# config-bank3.net
KiCad netlist of a schematic drawn in Altium Designer
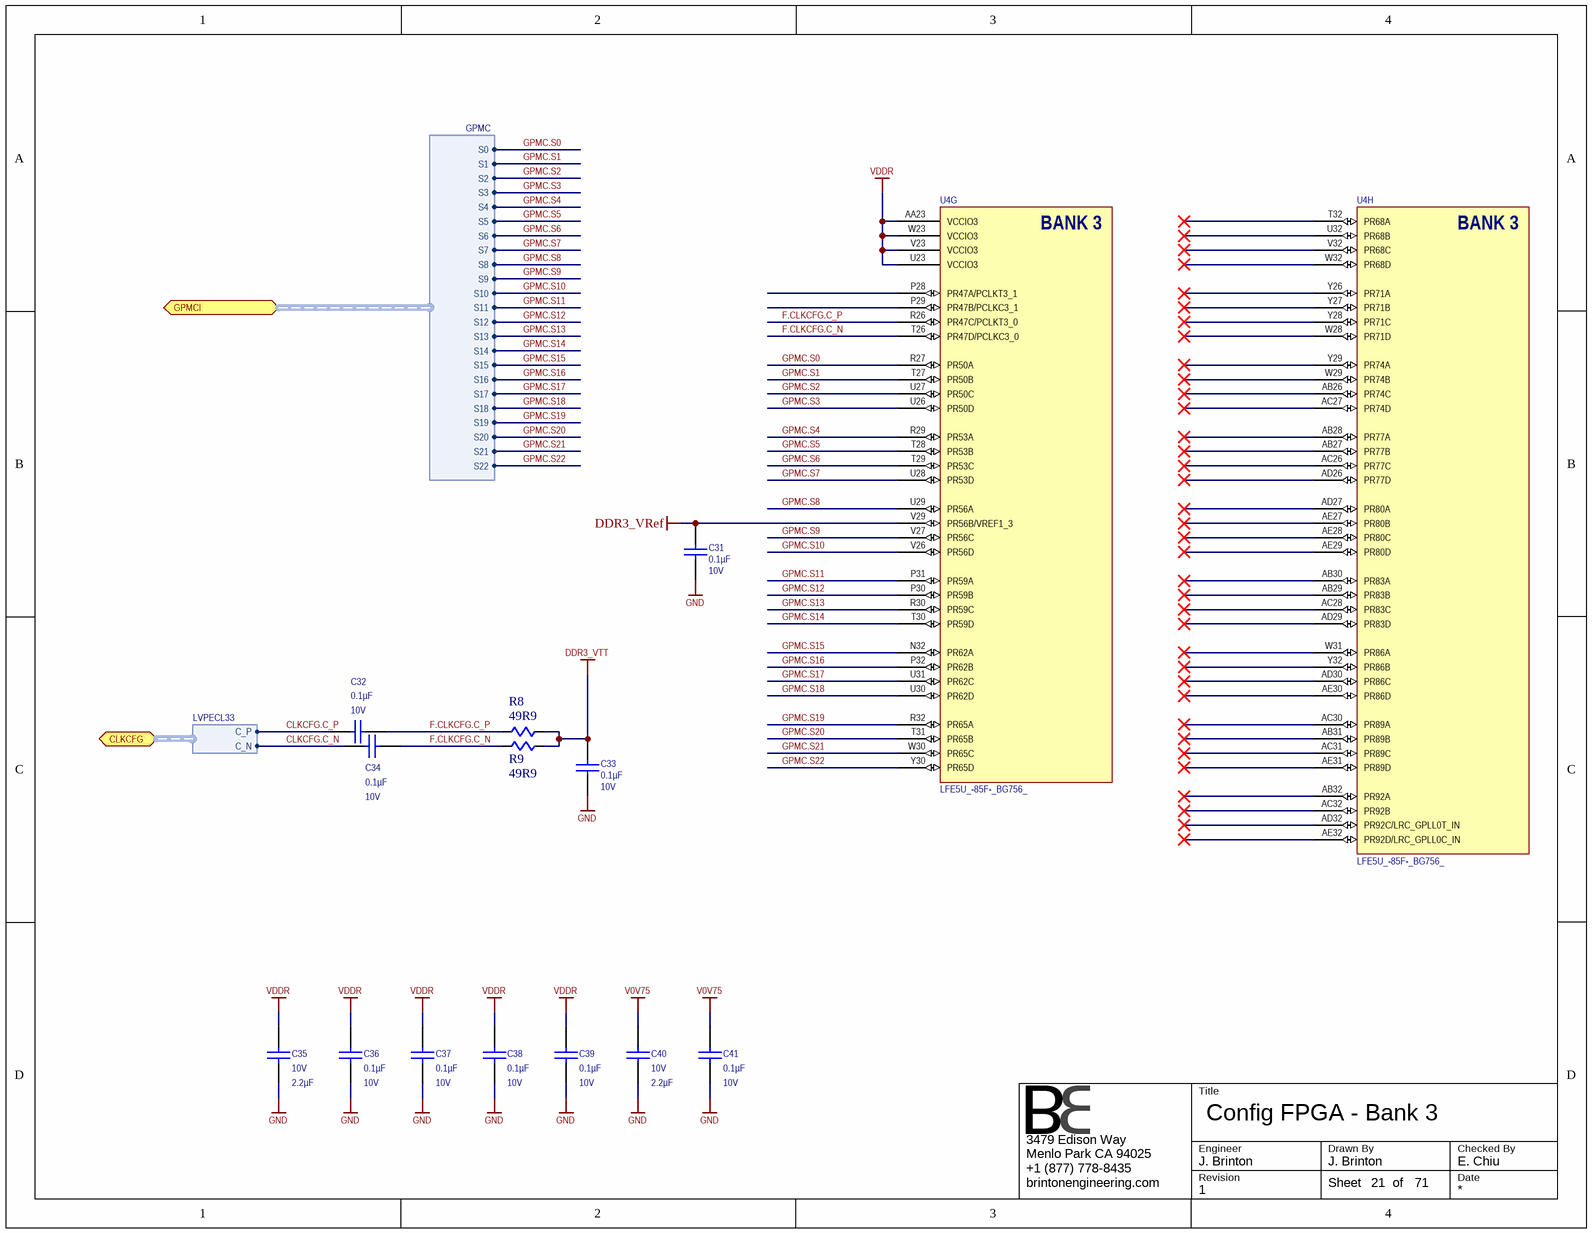
[diagram p0: config-bank3.SchDoc]

(export (version "E")
  (design (tool "Eeschema 10.0.6"))
  (components
    (comp (ref "C31")
      (value "GRM155R71A104KA01J")
      (footprint "CAPC1005X56N")
      (description "CAP CER 0.1UF 10V 10% X7R 0402")
      (fields
        (field (name "MANUFACTURER") "Murata Electronics North America")
        (field (name "TOLERANCE") "±10%")
        (field (name "CAPACITANCE") "0.1µF")
        (field (name "VOLTAGE - RATED") "10V")
      )
      (libsource (lib "murata") (part "GRM155R71A104KA01J"))
    )
    (comp (ref "C32")
      (value "GRM155R71A104KA01J")
      (footprint "CAPC1005X56N")
      (description "CAP CER 0.1UF 10V 10% X7R 0402")
      (fields
        (field (name "MANUFACTURER") "Murata Electronics North America")
        (field (name "TOLERANCE") "±10%")
        (field (name "CAPACITANCE") "0.1µF")
        (field (name "VOLTAGE - RATED") "10V")
      )
      (libsource (lib "murata") (part "GRM155R71A104KA01J"))
    )
    (comp (ref "C33")
      (value "GRM155R71A104KA01J")
      (footprint "CAPC1005X56N")
      (description "CAP CER 0.1UF 10V 10% X7R 0402")
      (fields
        (field (name "MANUFACTURER") "Murata Electronics North America")
        (field (name "TOLERANCE") "±10%")
        (field (name "CAPACITANCE") "0.1µF")
        (field (name "VOLTAGE - RATED") "10V")
      )
      (libsource (lib "murata") (part "GRM155R71A104KA01J"))
    )
    (comp (ref "C34")
      (value "GRM155R71A104KA01J")
      (footprint "CAPC1005X56N")
      (description "CAP CER 0.1UF 10V 10% X7R 0402")
      (fields
        (field (name "MANUFACTURER") "Murata Electronics North America")
        (field (name "TOLERANCE") "±10%")
        (field (name "CAPACITANCE") "0.1µF")
        (field (name "VOLTAGE - RATED") "10V")
      )
      (libsource (lib "murata") (part "GRM155R71A104KA01J"))
    )
    (comp (ref "C35")
      (value "GRM188R71A225KE15D")
      (footprint "CAPC1608X90N")
      (description "CAP CER 2.2UF 10V 10% X7R 0603")
      (fields
        (field (name "MANUFACTURER") "Murata Electronics North America")
        (field (name "TOLERANCE") "±10%")
        (field (name "VOLTAGE - RATED") "10V")
        (field (name "CAPACITANCE") "2.2µF")
      )
      (libsource (lib "murata") (part "GRM188R71A225KE15D"))
    )
    (comp (ref "C36")
      (value "GRM155R71A104KA01J")
      (footprint "CAPC1005X56N")
      (description "CAP CER 0.1UF 10V 10% X7R 0402")
      (fields
        (field (name "MANUFACTURER") "Murata Electronics North America")
        (field (name "TOLERANCE") "±10%")
        (field (name "CAPACITANCE") "0.1µF")
        (field (name "VOLTAGE - RATED") "10V")
      )
      (libsource (lib "murata") (part "GRM155R71A104KA01J"))
    )
    (comp (ref "C37")
      (value "GRM155R71A104KA01J")
      (footprint "CAPC1005X56N")
      (description "CAP CER 0.1UF 10V 10% X7R 0402")
      (fields
        (field (name "MANUFACTURER") "Murata Electronics North America")
        (field (name "TOLERANCE") "±10%")
        (field (name "CAPACITANCE") "0.1µF")
        (field (name "VOLTAGE - RATED") "10V")
      )
      (libsource (lib "murata") (part "GRM155R71A104KA01J"))
    )
    (comp (ref "C38")
      (value "GRM155R71A104KA01J")
      (footprint "CAPC1005X56N")
      (description "CAP CER 0.1UF 10V 10% X7R 0402")
      (fields
        (field (name "MANUFACTURER") "Murata Electronics North America")
        (field (name "TOLERANCE") "±10%")
        (field (name "CAPACITANCE") "0.1µF")
        (field (name "VOLTAGE - RATED") "10V")
      )
      (libsource (lib "murata") (part "GRM155R71A104KA01J"))
    )
    (comp (ref "C39")
      (value "GRM155R71A104KA01J")
      (footprint "CAPC1005X56N")
      (description "CAP CER 0.1UF 10V 10% X7R 0402")
      (fields
        (field (name "MANUFACTURER") "Murata Electronics North America")
        (field (name "TOLERANCE") "±10%")
        (field (name "CAPACITANCE") "0.1µF")
        (field (name "VOLTAGE - RATED") "10V")
      )
      (libsource (lib "murata") (part "GRM155R71A104KA01J"))
    )
    (comp (ref "C40")
      (value "GRM188R71A225KE15D")
      (footprint "CAPC1608X90N")
      (description "CAP CER 2.2UF 10V 10% X7R 0603")
      (fields
        (field (name "MANUFACTURER") "Murata Electronics North America")
        (field (name "TOLERANCE") "±10%")
        (field (name "VOLTAGE - RATED") "10V")
        (field (name "CAPACITANCE") "2.2µF")
      )
      (libsource (lib "murata") (part "GRM188R71A225KE15D"))
    )
    (comp (ref "C41")
      (value "GRM155R71A104KA01J")
      (footprint "CAPC1005X56N")
      (description "CAP CER 0.1UF 10V 10% X7R 0402")
      (fields
        (field (name "MANUFACTURER") "Murata Electronics North America")
        (field (name "TOLERANCE") "±10%")
        (field (name "CAPACITANCE") "0.1µF")
        (field (name "VOLTAGE - RATED") "10V")
      )
      (libsource (lib "murata") (part "GRM155R71A104KA01J"))
    )
    (comp (ref "R8")
      (value "49R9")
      (footprint "RESC1005N-0402")
      (description "Res 49.9R 1/10W 1% 0402")
      (fields (field (name "MFG") "Panasonic"))
      (libsource (lib "Kron Library Rev 3") (part "ERJ-2RKF49R9X"))
    )
    (comp (ref "R9")
      (value "49R9")
      (footprint "RESC1005N-0402")
      (description "Res 49.9R 1/10W 1% 0402")
      (fields (field (name "MFG") "Panasonic"))
      (libsource (lib "Kron Library Rev 3") (part "ERJ-2RKF49R9X"))
    )
    (comp (ref "U4")
      (value "LFE5U_-85F-_BG756_")
      (footprint "lattice:caBGA756")
      (description "ECP5 FPGA, 85k LUT, 756-caBGA")
      (fields (field (name "MANUFACTURER") "Lattice Semiconductor"))
      (libsource (lib "lattice") (part "LFE5U_-85F-_BG756_"))
    )
  )
  (nets
    (net (code "3") (name "/CLKCFG.C_N") (class "Default")
      (node (ref "C34") (pin "2") (pinfunction "2_2") (pintype "passive"))
    )
    (net (code "4") (name "/CLKCFG.C_P") (class "Default")
      (node (ref "C32") (pin "2") (pinfunction "2_2") (pintype "passive"))
    )
    (net (code "5") (name "/F.CLKCFG.C_N") (class "Default")
      (node (ref "C34") (pin "1") (pinfunction "1_1") (pintype "passive"))
      (node (ref "R9") (pin "1") (pintype "passive"))
      (node (ref "U4") (pin "T26") (pinfunction "PR47D/PCLKC3_0_T26") (pintype "bidirectional"))
    )
    (net (code "6") (name "/F.CLKCFG.C_P") (class "Default")
      (node (ref "C32") (pin "1") (pinfunction "1_1") (pintype "passive"))
      (node (ref "R8") (pin "1") (pintype "passive"))
      (node (ref "U4") (pin "R26") (pinfunction "PR47C/PCLKT3_0_R26") (pintype "bidirectional"))
    )
    (net (code "7") (name "/GPMC.S0") (class "Default")
      (node (ref "U4") (pin "R27") (pinfunction "PR50A_R27") (pintype "bidirectional"))
    )
    (net (code "8") (name "/GPMC.S1") (class "Default")
      (node (ref "U4") (pin "T27") (pinfunction "PR50B_T27") (pintype "bidirectional"))
    )
    (net (code "9") (name "/GPMC.S2") (class "Default")
      (node (ref "U4") (pin "U27") (pinfunction "PR50C_U27") (pintype "bidirectional"))
    )
    (net (code "10") (name "/GPMC.S3") (class "Default")
      (node (ref "U4") (pin "U26") (pinfunction "PR50D_U26") (pintype "bidirectional"))
    )
    (net (code "11") (name "/GPMC.S4") (class "Default")
      (node (ref "U4") (pin "R29") (pinfunction "PR53A_R29") (pintype "bidirectional"))
    )
    (net (code "12") (name "/GPMC.S5") (class "Default")
      (node (ref "U4") (pin "T28") (pinfunction "PR53B_T28") (pintype "bidirectional"))
    )
    (net (code "13") (name "/GPMC.S6") (class "Default")
      (node (ref "U4") (pin "T29") (pinfunction "PR53C_T29") (pintype "bidirectional"))
    )
    (net (code "14") (name "/GPMC.S7") (class "Default")
      (node (ref "U4") (pin "U28") (pinfunction "PR53D_U28") (pintype "bidirectional"))
    )
    (net (code "15") (name "/GPMC.S8") (class "Default")
      (node (ref "U4") (pin "U29") (pinfunction "PR56A_U29") (pintype "bidirectional"))
    )
    (net (code "16") (name "/GPMC.S9") (class "Default")
      (node (ref "U4") (pin "V27") (pinfunction "PR56C_V27") (pintype "bidirectional"))
    )
    (net (code "17") (name "/GPMC.S10") (class "Default")
      (node (ref "U4") (pin "V26") (pinfunction "PR56D_V26") (pintype "bidirectional"))
    )
    (net (code "18") (name "/GPMC.S11") (class "Default")
      (node (ref "U4") (pin "P31") (pinfunction "PR59A_P31") (pintype "bidirectional"))
    )
    (net (code "19") (name "/GPMC.S12") (class "Default")
      (node (ref "U4") (pin "P30") (pinfunction "PR59B_P30") (pintype "bidirectional"))
    )
    (net (code "20") (name "/GPMC.S13") (class "Default")
      (node (ref "U4") (pin "R30") (pinfunction "PR59C_R30") (pintype "bidirectional"))
    )
    (net (code "21") (name "/GPMC.S14") (class "Default")
      (node (ref "U4") (pin "T30") (pinfunction "PR59D_T30") (pintype "bidirectional"))
    )
    (net (code "22") (name "/GPMC.S15") (class "Default")
      (node (ref "U4") (pin "N32") (pinfunction "PR62A_N32") (pintype "bidirectional"))
    )
    (net (code "23") (name "/GPMC.S16") (class "Default")
      (node (ref "U4") (pin "P32") (pinfunction "PR62B_P32") (pintype "bidirectional"))
    )
    (net (code "24") (name "/GPMC.S17") (class "Default")
      (node (ref "U4") (pin "U31") (pinfunction "PR62C_U31") (pintype "bidirectional"))
    )
    (net (code "25") (name "/GPMC.S18") (class "Default")
      (node (ref "U4") (pin "U30") (pinfunction "PR62D_U30") (pintype "bidirectional"))
    )
    (net (code "26") (name "/GPMC.S19") (class "Default")
      (node (ref "U4") (pin "R32") (pinfunction "PR65A_R32") (pintype "bidirectional"))
    )
    (net (code "27") (name "/GPMC.S20") (class "Default")
      (node (ref "U4") (pin "T31") (pinfunction "PR65B_T31") (pintype "bidirectional"))
    )
    (net (code "28") (name "/GPMC.S21") (class "Default")
      (node (ref "U4") (pin "W30") (pinfunction "PR65C_W30") (pintype "bidirectional"))
    )
    (net (code "29") (name "/GPMC.S22") (class "Default")
      (node (ref "U4") (pin "Y30") (pinfunction "PR65D_Y30") (pintype "bidirectional"))
    )
    (net (code "32") (name "DDR3_VRef") (class "Default")
      (node (ref "C31") (pin "1") (pinfunction "1_1") (pintype "passive"))
      (node (ref "U4") (pin "V29") (pinfunction "PR56B/VREF1_3_V29") (pintype "bidirectional"))
    )
    (net (code "33") (name "DDR3_VTT") (class "Default")
      (node (ref "C33") (pin "2") (pinfunction "2_2") (pintype "passive"))
      (node (ref "R8") (pin "2") (pintype "passive"))
      (node (ref "R9") (pin "2") (pintype "passive"))
    )
    (net (code "34") (name "GND") (class "Default")
      (node (ref "C31") (pin "2") (pinfunction "2_2") (pintype "passive"))
      (node (ref "C33") (pin "1") (pinfunction "1_1") (pintype "passive"))
      (node (ref "C35") (pin "1") (pinfunction "1_1") (pintype "passive"))
      (node (ref "C36") (pin "1") (pinfunction "1_1") (pintype "passive"))
      (node (ref "C37") (pin "1") (pinfunction "1_1") (pintype "passive"))
      (node (ref "C38") (pin "1") (pinfunction "1_1") (pintype "passive"))
      (node (ref "C39") (pin "1") (pinfunction "1_1") (pintype "passive"))
      (node (ref "C40") (pin "1") (pinfunction "1_1") (pintype "passive"))
      (node (ref "C41") (pin "1") (pinfunction "1_1") (pintype "passive"))
    )
    (net (code "35") (name "V0V75") (class "Default")
      (node (ref "C40") (pin "2") (pinfunction "2_2") (pintype "passive"))
      (node (ref "C41") (pin "2") (pinfunction "2_2") (pintype "passive"))
    )
    (net (code "36") (name "VDDR") (class "Default")
      (node (ref "C35") (pin "2") (pinfunction "2_2") (pintype "passive"))
      (node (ref "C36") (pin "2") (pinfunction "2_2") (pintype "passive"))
      (node (ref "C37") (pin "2") (pinfunction "2_2") (pintype "passive"))
      (node (ref "C38") (pin "2") (pinfunction "2_2") (pintype "passive"))
      (node (ref "C39") (pin "2") (pinfunction "2_2") (pintype "passive"))
      (node (ref "U4") (pin "AA23") (pinfunction "VCCIO3_AA23") (pintype "power_in"))
      (node (ref "U4") (pin "U23") (pinfunction "VCCIO3_U23") (pintype "power_in"))
      (node (ref "U4") (pin "V23") (pinfunction "VCCIO3_V23") (pintype "power_in"))
      (node (ref "U4") (pin "W23") (pinfunction "VCCIO3_W23") (pintype "power_in"))
    )
    (net (code "37") (name "unconnected-(U4G-PR47A{slash}PCLKT3_1-PadP28)") (class "Default")
      (node (ref "U4") (pin "P28") (pinfunction "PR47A/PCLKT3_1_P28") (pintype "bidirectional"))
    )
    (net (code "38") (name "unconnected-(U4G-PR47B{slash}PCLKC3_1-PadP29)") (class "Default")
      (node (ref "U4") (pin "P29") (pinfunction "PR47B/PCLKC3_1_P29") (pintype "bidirectional"))
    )
    (net (code "39") (name "unconnected-(U4H-PR68A-PadT32)") (class "Default")
      (node (ref "U4") (pin "T32") (pinfunction "PR68A_T32") (pintype "bidirectional+no_connect"))
    )
    (net (code "40") (name "unconnected-(U4H-PR68B-PadU32)") (class "Default")
      (node (ref "U4") (pin "U32") (pinfunction "PR68B_U32") (pintype "bidirectional+no_connect"))
    )
    (net (code "41") (name "unconnected-(U4H-PR68C-PadV32)") (class "Default")
      (node (ref "U4") (pin "V32") (pinfunction "PR68C_V32") (pintype "bidirectional+no_connect"))
    )
    (net (code "42") (name "unconnected-(U4H-PR68D-PadW32)") (class "Default")
      (node (ref "U4") (pin "W32") (pinfunction "PR68D_W32") (pintype "bidirectional+no_connect"))
    )
    (net (code "43") (name "unconnected-(U4H-PR71A-PadY26)") (class "Default")
      (node (ref "U4") (pin "Y26") (pinfunction "PR71A_Y26") (pintype "bidirectional+no_connect"))
    )
    (net (code "44") (name "unconnected-(U4H-PR71B-PadY27)") (class "Default")
      (node (ref "U4") (pin "Y27") (pinfunction "PR71B_Y27") (pintype "bidirectional+no_connect"))
    )
    (net (code "45") (name "unconnected-(U4H-PR71C-PadY28)") (class "Default")
      (node (ref "U4") (pin "Y28") (pinfunction "PR71C_Y28") (pintype "bidirectional+no_connect"))
    )
    (net (code "46") (name "unconnected-(U4H-PR71D-PadW28)") (class "Default")
      (node (ref "U4") (pin "W28") (pinfunction "PR71D_W28") (pintype "bidirectional+no_connect"))
    )
    (net (code "47") (name "unconnected-(U4H-PR74A-PadY29)") (class "Default")
      (node (ref "U4") (pin "Y29") (pinfunction "PR74A_Y29") (pintype "bidirectional+no_connect"))
    )
    (net (code "48") (name "unconnected-(U4H-PR74B-PadW29)") (class "Default")
      (node (ref "U4") (pin "W29") (pinfunction "PR74B_W29") (pintype "bidirectional+no_connect"))
    )
    (net (code "49") (name "unconnected-(U4H-PR74C-PadAB26)") (class "Default")
      (node (ref "U4") (pin "AB26") (pinfunction "PR74C_AB26") (pintype "bidirectional+no_connect"))
    )
    (net (code "50") (name "unconnected-(U4H-PR74D-PadAC27)") (class "Default")
      (node (ref "U4") (pin "AC27") (pinfunction "PR74D_AC27") (pintype "bidirectional+no_connect"))
    )
    (net (code "51") (name "unconnected-(U4H-PR77A-PadAB28)") (class "Default")
      (node (ref "U4") (pin "AB28") (pinfunction "PR77A_AB28") (pintype "bidirectional+no_connect"))
    )
    (net (code "52") (name "unconnected-(U4H-PR77B-PadAB27)") (class "Default")
      (node (ref "U4") (pin "AB27") (pinfunction "PR77B_AB27") (pintype "bidirectional+no_connect"))
    )
    (net (code "53") (name "unconnected-(U4H-PR77C-PadAC26)") (class "Default")
      (node (ref "U4") (pin "AC26") (pinfunction "PR77C_AC26") (pintype "bidirectional+no_connect"))
    )
    (net (code "54") (name "unconnected-(U4H-PR77D-PadAD26)") (class "Default")
      (node (ref "U4") (pin "AD26") (pinfunction "PR77D_AD26") (pintype "bidirectional+no_connect"))
    )
    (net (code "55") (name "unconnected-(U4H-PR80A-PadAD27)") (class "Default")
      (node (ref "U4") (pin "AD27") (pinfunction "PR80A_AD27") (pintype "bidirectional+no_connect"))
    )
    (net (code "56") (name "unconnected-(U4H-PR80B-PadAE27)") (class "Default")
      (node (ref "U4") (pin "AE27") (pinfunction "PR80B_AE27") (pintype "bidirectional+no_connect"))
    )
    (net (code "57") (name "unconnected-(U4H-PR80C-PadAE28)") (class "Default")
      (node (ref "U4") (pin "AE28") (pinfunction "PR80C_AE28") (pintype "bidirectional+no_connect"))
    )
    (net (code "58") (name "unconnected-(U4H-PR80D-PadAE29)") (class "Default")
      (node (ref "U4") (pin "AE29") (pinfunction "PR80D_AE29") (pintype "bidirectional+no_connect"))
    )
    (net (code "59") (name "unconnected-(U4H-PR83A-PadAB30)") (class "Default")
      (node (ref "U4") (pin "AB30") (pinfunction "PR83A_AB30") (pintype "bidirectional+no_connect"))
    )
    (net (code "60") (name "unconnected-(U4H-PR83B-PadAB29)") (class "Default")
      (node (ref "U4") (pin "AB29") (pinfunction "PR83B_AB29") (pintype "bidirectional+no_connect"))
    )
    (net (code "61") (name "unconnected-(U4H-PR83C-PadAC28)") (class "Default")
      (node (ref "U4") (pin "AC28") (pinfunction "PR83C_AC28") (pintype "bidirectional+no_connect"))
    )
    (net (code "62") (name "unconnected-(U4H-PR83D-PadAD29)") (class "Default")
      (node (ref "U4") (pin "AD29") (pinfunction "PR83D_AD29") (pintype "bidirectional+no_connect"))
    )
    (net (code "63") (name "unconnected-(U4H-PR86A-PadW31)") (class "Default")
      (node (ref "U4") (pin "W31") (pinfunction "PR86A_W31") (pintype "bidirectional+no_connect"))
    )
    (net (code "64") (name "unconnected-(U4H-PR86B-PadY32)") (class "Default")
      (node (ref "U4") (pin "Y32") (pinfunction "PR86B_Y32") (pintype "bidirectional+no_connect"))
    )
    (net (code "65") (name "unconnected-(U4H-PR86C-PadAD30)") (class "Default")
      (node (ref "U4") (pin "AD30") (pinfunction "PR86C_AD30") (pintype "bidirectional+no_connect"))
    )
    (net (code "66") (name "unconnected-(U4H-PR86D-PadAE30)") (class "Default")
      (node (ref "U4") (pin "AE30") (pinfunction "PR86D_AE30") (pintype "bidirectional+no_connect"))
    )
    (net (code "67") (name "unconnected-(U4H-PR89A-PadAC30)") (class "Default")
      (node (ref "U4") (pin "AC30") (pinfunction "PR89A_AC30") (pintype "bidirectional+no_connect"))
    )
    (net (code "68") (name "unconnected-(U4H-PR89B-PadAB31)") (class "Default")
      (node (ref "U4") (pin "AB31") (pinfunction "PR89B_AB31") (pintype "bidirectional+no_connect"))
    )
    (net (code "69") (name "unconnected-(U4H-PR89C-PadAC31)") (class "Default")
      (node (ref "U4") (pin "AC31") (pinfunction "PR89C_AC31") (pintype "bidirectional+no_connect"))
    )
    (net (code "70") (name "unconnected-(U4H-PR89D-PadAE31)") (class "Default")
      (node (ref "U4") (pin "AE31") (pinfunction "PR89D_AE31") (pintype "bidirectional+no_connect"))
    )
    (net (code "71") (name "unconnected-(U4H-PR92A-PadAB32)") (class "Default")
      (node (ref "U4") (pin "AB32") (pinfunction "PR92A_AB32") (pintype "bidirectional+no_connect"))
    )
    (net (code "72") (name "unconnected-(U4H-PR92B-PadAC32)") (class "Default")
      (node (ref "U4") (pin "AC32") (pinfunction "PR92B_AC32") (pintype "bidirectional+no_connect"))
    )
    (net (code "73") (name "unconnected-(U4H-PR92C{slash}LRC_GPLL0T_IN-PadAD32)") (class "Default")
      (node (ref "U4") (pin "AD32") (pinfunction "PR92C/LRC_GPLL0T_IN_AD32") (pintype "bidirectional+no_connect"))
    )
    (net (code "74") (name "unconnected-(U4H-PR92D{slash}LRC_GPLL0C_IN-PadAE32)") (class "Default")
      (node (ref "U4") (pin "AE32") (pinfunction "PR92D/LRC_GPLL0C_IN_AE32") (pintype "bidirectional+no_connect"))
    )
  )
)
